# STM32F103c8t6.net
KiCad netlist of a schematic drawn in EasyEDA Pro
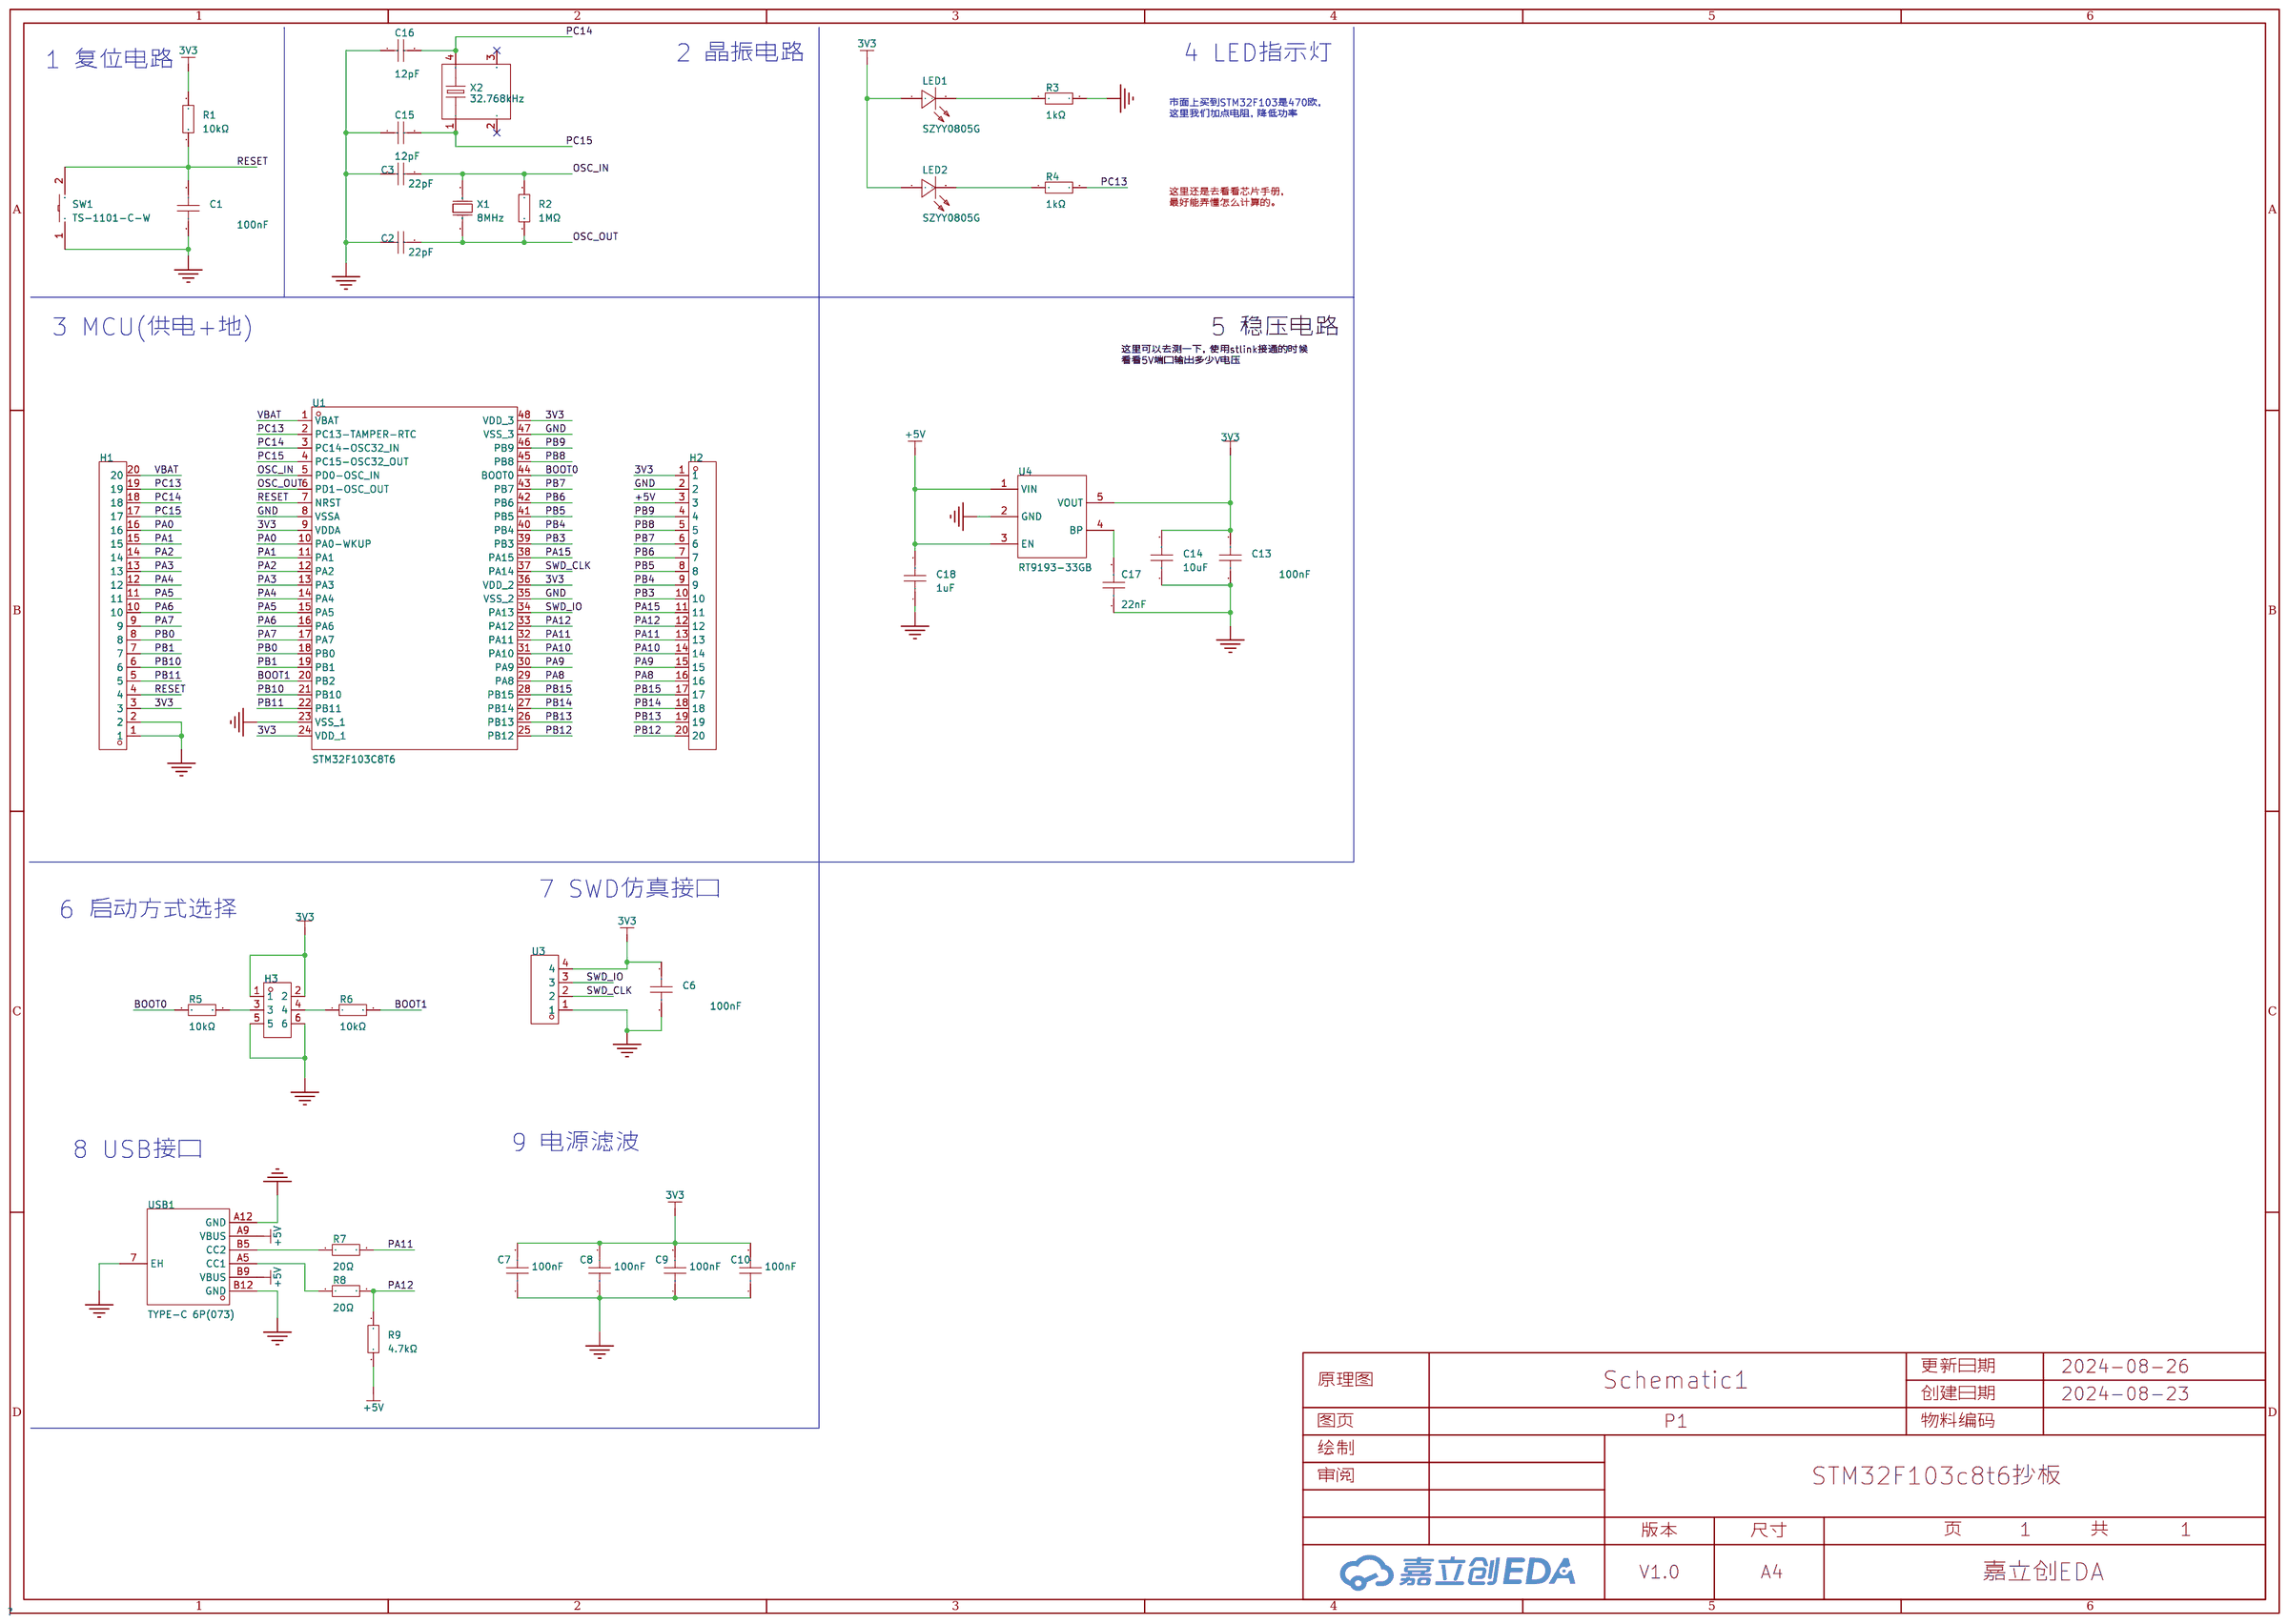
[diagram p0: schematic sheet]

(export (version "E")
  (design (tool "Eeschema 10.0.6"))
  (components
    (comp (ref "C1")
      (value "100nF")
      (footprint "easyedapro:C0603")
      (description "容值:100nF;精度:±10%;额定电压:50V;材质(温度系数):X7R;")
      (fields
        (field (name "Manufacturer Part") "CGA0603X7R104K500JT")
        (field (name "Manufacturer") "HRE(芯声)")
      )
      (libsource (lib "easyedapro") (part "CGA0603X7R104K500JT"))
    )
    (comp (ref "C2")
      (value "22pF")
      (footprint "easyedapro:C0603")
      (description "容值:22pF;精度:±5%;额定电压:50V;材质(温度系数):C0G;")
      (fields
        (field (name "Manufacturer Part") "CL10C220JB8NNNC")
        (field (name "Manufacturer") "SAMSUNG(三星)")
      )
      (libsource (lib "easyedapro") (part "CL10C220JB8NNNC"))
    )
    (comp (ref "C3")
      (value "22pF")
      (footprint "easyedapro:C0603")
      (description "容值:22pF;精度:±5%;额定电压:50V;材质(温度系数):C0G;")
      (fields
        (field (name "Manufacturer Part") "CL10C220JB8NNNC")
        (field (name "Manufacturer") "SAMSUNG(三星)")
      )
      (libsource (lib "easyedapro") (part "CL10C220JB8NNNC"))
    )
    (comp (ref "C6")
      (value "100nF")
      (footprint "easyedapro:C0603")
      (description "容值:100nF;精度:±10%;额定电压:50V;材质(温度系数):X7R;")
      (fields
        (field (name "Manufacturer Part") "CGA0603X7R104K500JT")
        (field (name "Manufacturer") "HRE(芯声)")
      )
      (libsource (lib "easyedapro") (part "CGA0603X7R104K500JT"))
    )
    (comp (ref "C7")
      (value "100nF")
      (footprint "easyedapro:C0603")
      (description "容值:100nF;精度:±10%;额定电压:50V;材质(温度系数):X7R;")
      (fields
        (field (name "Manufacturer Part") "CGA0603X7R104K500JT")
        (field (name "Manufacturer") "HRE(芯声)")
      )
      (libsource (lib "easyedapro") (part "CGA0603X7R104K500JT"))
    )
    (comp (ref "C8")
      (value "100nF")
      (footprint "easyedapro:C0603")
      (description "容值:100nF;精度:±10%;额定电压:50V;材质(温度系数):X7R;")
      (fields
        (field (name "Manufacturer Part") "CGA0603X7R104K500JT")
        (field (name "Manufacturer") "HRE(芯声)")
      )
      (libsource (lib "easyedapro") (part "CGA0603X7R104K500JT"))
    )
    (comp (ref "C9")
      (value "100nF")
      (footprint "easyedapro:C0603")
      (description "容值:100nF;精度:±10%;额定电压:50V;材质(温度系数):X7R;")
      (fields
        (field (name "Manufacturer Part") "CGA0603X7R104K500JT")
        (field (name "Manufacturer") "HRE(芯声)")
      )
      (libsource (lib "easyedapro") (part "CGA0603X7R104K500JT"))
    )
    (comp (ref "C10")
      (value "100nF")
      (footprint "easyedapro:C0603")
      (description "容值:100nF;精度:±10%;额定电压:50V;材质(温度系数):X7R;")
      (fields
        (field (name "Manufacturer Part") "CGA0603X7R104K500JT")
        (field (name "Manufacturer") "HRE(芯声)")
      )
      (libsource (lib "easyedapro") (part "CGA0603X7R104K500JT"))
    )
    (comp (ref "C13")
      (value "100nF")
      (footprint "easyedapro:C0603")
      (description "容值:100nF;精度:±10%;额定电压:50V;材质(温度系数):X7R;")
      (fields
        (field (name "Manufacturer Part") "CGA0603X7R104K500JT")
        (field (name "Manufacturer") "HRE(芯声)")
      )
      (libsource (lib "easyedapro") (part "CGA0603X7R104K500JT"))
    )
    (comp (ref "C14")
      (value "10uF")
      (footprint "easyedapro:C0603")
      (description "容值:10uF;精度:±20%;额定电压:35V;材质(温度系数):X5R;")
      (fields
        (field (name "Manufacturer Part") "GRM188R6YA106MA73D")
        (field (name "Manufacturer") "muRata(村田)")
      )
      (libsource (lib "easyedapro") (part "GRM188R6YA106MA73D"))
    )
    (comp (ref "C15")
      (value "12pF")
      (footprint "easyedapro:C0603")
      (description "容值:12pF;精度:±5%;额定电压:50V;材质(温度系数):C0G;")
      (fields
        (field (name "Manufacturer Part") "CL10C120JB8NNNC")
        (field (name "Manufacturer") "SAMSUNG(三星)")
      )
      (libsource (lib "easyedapro") (part "CL10C120JB8NNNC"))
    )
    (comp (ref "C16")
      (value "12pF")
      (footprint "easyedapro:C0603")
      (description "容值:12pF;精度:±5%;额定电压:50V;材质(温度系数):C0G;")
      (fields
        (field (name "Manufacturer Part") "CL10C120JB8NNNC")
        (field (name "Manufacturer") "SAMSUNG(三星)")
      )
      (libsource (lib "easyedapro") (part "CL10C120JB8NNNC"))
    )
    (comp (ref "C17")
      (value "22nF")
      (footprint "easyedapro:C0603")
      (description "容值:22nF;精度:±10%;额定电压:100V;材质(温度系数):X7R;")
      (fields
        (field (name "Manufacturer Part") "CC0603KRX7R0BB223")
        (field (name "Manufacturer") "YAGEO(国巨)")
      )
      (libsource (lib "easyedapro") (part "CC0603KRX7R0BB223"))
    )
    (comp (ref "C18")
      (value "1uF")
      (footprint "easyedapro:C0603")
      (description "容值:1uF;精度:±10%;额定电压:50V;材质(温度系数):X5R;")
      (fields
        (field (name "Manufacturer Part") "CL10A105KB8NNNC")
        (field (name "Manufacturer") "SAMSUNG(三星)")
      )
      (libsource (lib "easyedapro") (part "CL10A105KB8NNNC"))
    )
    (comp (ref "H1")
      (value "X6511WV-20H-C60D30")
      (footprint "easyedapro:HDR-TH_20P-P2.54-V-M")
      (fields (field (name "Manufacturer") "XKB Connection(中国星坤)"))
      (libsource (lib "easyedapro") (part "X6511WV-20H-C30D60"))
    )
    (comp (ref "H2")
      (value "X6511WV-20H-C60D30")
      (footprint "easyedapro:HDR-TH_20P-P2.54-V-M")
      (fields (field (name "Manufacturer") "XKB Connection(中国星坤)"))
      (libsource (lib "easyedapro") (part "X6511WV-20H-C30D60"))
    )
    (comp (ref "H3")
      (value "PZ254-2-03-Z-8.5")
      (footprint "easyedapro:HDR-TH_6P-P2.54-V-M-R2-C3-S2.54")
      (fields (field (name "Manufacturer") "HCTL(华灿天禄)"))
      (libsource (lib "easyedapro") (part "PZ254-2-03-Z-8.5"))
    )
    (comp (ref "LED1")
      (value "SZYY0805G")
      (footprint "easyedapro:LED0805-R-RD")
      (description "发光颜色:翠绿色;")
      (fields (field (name "Manufacturer") "yongyu(永裕光电)"))
      (libsource (lib "easyedapro") (part "SZYY0805G"))
    )
    (comp (ref "LED2")
      (value "SZYY0805G")
      (footprint "easyedapro:LED0805-R-RD")
      (description "发光颜色:翠绿色;")
      (fields (field (name "Manufacturer") "yongyu(永裕光电)"))
      (libsource (lib "easyedapro") (part "SZYY0805G"))
    )
    (comp (ref "R1")
      (value "10kΩ")
      (footprint "easyedapro:R0603")
      (description "电阻类型:厚膜电阻;阻值:10kΩ;精度:±1%;功率:100mW;最大工作电压:75V;温度系数:±100ppm/°C;")
      (fields
        (field (name "Manufacturer Part") "0603WAF1002T5E")
        (field (name "Manufacturer") "UNI-ROYAL(厚声)")
      )
      (libsource (lib "easyedapro") (part "0603WAF1002T5E"))
    )
    (comp (ref "R2")
      (value "1MΩ")
      (footprint "easyedapro:R0603")
      (description "电阻类型:厚膜电阻;阻值:1MΩ;精度:±1%;功率:100mW;最大工作电压:75V;温度系数:±100ppm/°C;")
      (fields
        (field (name "Manufacturer Part") "0603WAF1004T5E")
        (field (name "Manufacturer") "UNI-ROYAL(厚声)")
      )
      (libsource (lib "easyedapro") (part "0603WAF1004T5E"))
    )
    (comp (ref "R3")
      (value "1kΩ")
      (footprint "easyedapro:R0603")
      (description "电阻类型:厚膜电阻;阻值:1kΩ;精度:±1%;功率:100mW;最大工作电压:75V;温度系数:±100ppm/°C;")
      (fields
        (field (name "Manufacturer Part") "0603WAF1001T5E")
        (field (name "Manufacturer") "UNI-ROYAL(厚声)")
      )
      (libsource (lib "easyedapro") (part "0603WAF1001T5E"))
    )
    (comp (ref "R4")
      (value "1kΩ")
      (footprint "easyedapro:R0603")
      (description "电阻类型:厚膜电阻;阻值:1kΩ;精度:±1%;功率:100mW;最大工作电压:75V;温度系数:±100ppm/°C;")
      (fields
        (field (name "Manufacturer Part") "0603WAF1001T5E")
        (field (name "Manufacturer") "UNI-ROYAL(厚声)")
      )
      (libsource (lib "easyedapro") (part "0603WAF1001T5E"))
    )
    (comp (ref "R5")
      (value "10kΩ")
      (footprint "easyedapro:R0603")
      (description "电阻类型:厚膜电阻;阻值:10kΩ;精度:±1%;功率:100mW;最大工作电压:75V;温度系数:±100ppm/°C;")
      (fields
        (field (name "Manufacturer Part") "0603WAF1002T5E")
        (field (name "Manufacturer") "UNI-ROYAL(厚声)")
      )
      (libsource (lib "easyedapro") (part "0603WAF1002T5E"))
    )
    (comp (ref "R6")
      (value "10kΩ")
      (footprint "easyedapro:R0603")
      (description "电阻类型:厚膜电阻;阻值:10kΩ;精度:±1%;功率:100mW;最大工作电压:75V;温度系数:±100ppm/°C;")
      (fields
        (field (name "Manufacturer Part") "0603WAF1002T5E")
        (field (name "Manufacturer") "UNI-ROYAL(厚声)")
      )
      (libsource (lib "easyedapro") (part "0603WAF1002T5E"))
    )
    (comp (ref "R7")
      (value "20Ω")
      (footprint "easyedapro:R0603")
      (description "电阻类型:厚膜电阻;阻值:20Ω;精度:±1%;功率:100mW;最大工作电压:75V;温度系数:±100ppm/°C;")
      (fields
        (field (name "Manufacturer Part") "0603WAF200JT5E")
        (field (name "Manufacturer") "UNI-ROYAL(厚声)")
      )
      (libsource (lib "easyedapro") (part "0603WAF200JT5E"))
    )
    (comp (ref "R8")
      (value "20Ω")
      (footprint "easyedapro:R0603")
      (description "电阻类型:厚膜电阻;阻值:20Ω;精度:±1%;功率:100mW;最大工作电压:75V;温度系数:±100ppm/°C;")
      (fields
        (field (name "Manufacturer Part") "0603WAF200JT5E")
        (field (name "Manufacturer") "UNI-ROYAL(厚声)")
      )
      (libsource (lib "easyedapro") (part "0603WAF200JT5E"))
    )
    (comp (ref "R9")
      (value "4.7kΩ")
      (footprint "easyedapro:R0603")
      (description "电阻类型:厚膜电阻;阻值:4.7kΩ;精度:±1%;功率:100mW;最大工作电压:75V;温度系数:±100ppm/°C;")
      (fields
        (field (name "Manufacturer Part") "0603WAF4701T5E")
        (field (name "Manufacturer") "UNI-ROYAL(厚声)")
      )
      (libsource (lib "easyedapro") (part "0603WAF4701T5E"))
    )
    (comp (ref "SW1")
      (value "TS-1101-C-W")
      (footprint "easyedapro:SW-SMD_L6.0-W3.3-LS8.0")
      (fields (field (name "Manufacturer") "XKB Connectivity(中国星坤)"))
      (libsource (lib "easyedapro") (part "TS-1101-C-W"))
    )
    (comp (ref "U1")
      (value "STM32F103C8T6")
      (footprint "easyedapro:LQFP-48_L7.0-W7.0-P0.50-LS9.0-BL")
      (description "CPU内核:ARM-M3;程序存储容量:64KB;RAM总容量:20KB;GPIO端口数量:37;工作电压范围:2V~3.6V;CPU最大主频:72MHz;程序存储器类型:FLASH;")
      (fields (field (name "Manufacturer") "ST(意法半导体)"))
      (libsource (lib "easyedapro") (part "STM32F103C8T6"))
    )
    (comp (ref "U3")
      (value "HB-PH3-25414PB2GOP")
      (footprint "easyedapro:HDR-TH_4P-P2.54-V-M")
      (fields (field (name "Manufacturer") "HANBO(汉博)"))
      (libsource (lib "easyedapro") (part "HB-PH3-25414PB2GOP"))
    )
    (comp (ref "U4")
      (value "RT9193-33GB")
      (footprint "easyedapro:SOT-23-5_L3.0-W1.7-P0.95-LS2.8-BL")
      (description "输出类型:固定;最大输入电压:5.5V;输出电压:3.3V;最大输出电流:300mA;电源纹波抑制比(PSRR):70dB;输出极性:正极;")
      (fields (field (name "Manufacturer") "RICHTEK(立锜)"))
      (libsource (lib "easyedapro") (part "RT9193-33GB"))
    )
    (comp (ref "USB1")
      (value "TYPE-C 6P(073)")
      (footprint "easyedapro:TYPE-C-SMD_TYPE-C-6P_5")
      (description "连接器类型:Type-C;标准:-;公母:母;端口数量:1;触点数量:6P;安装方式:卧贴;额定电流 - 电源:5A;工作温度范围:-25°C~+85°C;")
      (fields (field (name "Manufacturer") "SHOU HAN(首韩)"))
      (libsource (lib "easyedapro") (part "TYPE-C 6P(073)"))
    )
    (comp (ref "X1")
      (value "8MHz")
      (footprint "easyedapro:OSC-TH_L10.0-W4.5-P5.00")
      (description "晶振类型:直插晶振;频率:8MHz;常温频差:±20ppm;外接负载电容:20pF;频率稳定度(全温):±30ppm;")
      (fields (field (name "Manufacturer Part") "X49SD8MSD2SC") (field (name "Manufacturer") "YXC(扬兴晶振)"))
      (libsource (lib "easyedapro") (part "X49SD8MSD2SC"))
    )
    (comp (ref "X2")
      (value "32.768kHz")
      (footprint "easyedapro:MC-306_4P-L8.0-W3.2-P5.5-BL")
      (description "晶振类型:贴片晶振;频率:32.768kHz;常温频差:±20ppm;外接负载电容:6pF;")
      (fields (field (name "Manufacturer Part") "Q13MC30620006") (field (name "Manufacturer") "EPSON(爱普生)"))
      (libsource (lib "easyedapro") (part "MC-306 32.768kHz 6.0pF 20ppm"))
    )
  )
  (nets
    (net (code "1") (name "+5V") (class "Default")
      (node (ref "C18") (pin "2") (pinfunction "2_2") (pintype "unspecified"))
      (node (ref "H2") (pin "3") (pinfunction "3_3") (pintype "unspecified"))
      (node (ref "R9") (pin "1") (pinfunction "1_1") (pintype "input"))
      (node (ref "U4") (pin "1") (pinfunction "VIN_1") (pintype "unspecified"))
      (node (ref "U4") (pin "3") (pinfunction "EN_3") (pintype "unspecified"))
      (node (ref "USB1") (pin "A9") (pinfunction "VBUS_A9") (pintype "unspecified"))
      (node (ref "USB1") (pin "B9") (pinfunction "VBUS_B9") (pintype "unspecified"))
    )
    (net (code "2") (name "/BOOT0") (class "Default")
      (node (ref "R5") (pin "1") (pinfunction "1_1") (pintype "input"))
      (node (ref "U1") (pin "44") (pinfunction "BOOT0_44") (pintype "unspecified"))
    )
    (net (code "3") (name "/BOOT1") (class "Default")
      (node (ref "R6") (pin "2") (pinfunction "2_2") (pintype "input"))
      (node (ref "U1") (pin "20") (pinfunction "PB2_20") (pintype "unspecified"))
    )
    (net (code "4") (name "/OSC_IN") (class "Default")
      (node (ref "C3") (pin "2") (pinfunction "2_2") (pintype "input"))
      (node (ref "R2") (pin "2") (pinfunction "2_2") (pintype "input"))
      (node (ref "U1") (pin "5") (pinfunction "PD0-OSC_IN_5") (pintype "unspecified"))
      (node (ref "X1") (pin "1") (pinfunction "OSC1_1") (pintype "input"))
    )
    (net (code "5") (name "/OSC_OUT") (class "Default")
      (node (ref "C2") (pin "2") (pinfunction "2_2") (pintype "input"))
      (node (ref "R2") (pin "1") (pinfunction "1_1") (pintype "input"))
      (node (ref "U1") (pin "6") (pinfunction "PD1-OSC_OUT_6") (pintype "unspecified"))
      (node (ref "X1") (pin "2") (pinfunction "OSC2_2") (pintype "input"))
    )
    (net (code "6") (name "/PA0") (class "Default")
      (node (ref "H1") (pin "16") (pinfunction "16_16") (pintype "unspecified"))
      (node (ref "U1") (pin "10") (pinfunction "PA0-WKUP_10") (pintype "unspecified"))
    )
    (net (code "7") (name "/PA1") (class "Default")
      (node (ref "H1") (pin "15") (pinfunction "15_15") (pintype "unspecified"))
      (node (ref "U1") (pin "11") (pinfunction "PA1_11") (pintype "unspecified"))
    )
    (net (code "8") (name "/PA2") (class "Default")
      (node (ref "H1") (pin "14") (pinfunction "14_14") (pintype "unspecified"))
      (node (ref "U1") (pin "12") (pinfunction "PA2_12") (pintype "unspecified"))
    )
    (net (code "9") (name "/PA3") (class "Default")
      (node (ref "H1") (pin "13") (pinfunction "13_13") (pintype "unspecified"))
      (node (ref "U1") (pin "13") (pinfunction "PA3_13") (pintype "unspecified"))
    )
    (net (code "10") (name "/PA4") (class "Default")
      (node (ref "H1") (pin "12") (pinfunction "12_12") (pintype "unspecified"))
      (node (ref "U1") (pin "14") (pinfunction "PA4_14") (pintype "unspecified"))
    )
    (net (code "11") (name "/PA5") (class "Default")
      (node (ref "H1") (pin "11") (pinfunction "11_11") (pintype "unspecified"))
      (node (ref "U1") (pin "15") (pinfunction "PA5_15") (pintype "unspecified"))
    )
    (net (code "12") (name "/PA6") (class "Default")
      (node (ref "H1") (pin "10") (pinfunction "10_10") (pintype "unspecified"))
      (node (ref "U1") (pin "16") (pinfunction "PA6_16") (pintype "unspecified"))
    )
    (net (code "13") (name "/PA7") (class "Default")
      (node (ref "H1") (pin "9") (pinfunction "9_9") (pintype "unspecified"))
      (node (ref "U1") (pin "17") (pinfunction "PA7_17") (pintype "unspecified"))
    )
    (net (code "14") (name "/PA8") (class "Default")
      (node (ref "H2") (pin "16") (pinfunction "16_16") (pintype "unspecified"))
      (node (ref "U1") (pin "29") (pinfunction "PA8_29") (pintype "unspecified"))
    )
    (net (code "15") (name "/PA9") (class "Default")
      (node (ref "H2") (pin "15") (pinfunction "15_15") (pintype "unspecified"))
      (node (ref "U1") (pin "30") (pinfunction "PA9_30") (pintype "unspecified"))
    )
    (net (code "16") (name "/PA10") (class "Default")
      (node (ref "H2") (pin "14") (pinfunction "14_14") (pintype "unspecified"))
      (node (ref "U1") (pin "31") (pinfunction "PA10_31") (pintype "unspecified"))
    )
    (net (code "17") (name "/PA11") (class "Default")
      (node (ref "H2") (pin "13") (pinfunction "13_13") (pintype "unspecified"))
      (node (ref "R7") (pin "2") (pinfunction "2_2") (pintype "input"))
      (node (ref "U1") (pin "32") (pinfunction "PA11_32") (pintype "unspecified"))
    )
    (net (code "18") (name "/PA12") (class "Default")
      (node (ref "H2") (pin "12") (pinfunction "12_12") (pintype "unspecified"))
      (node (ref "R8") (pin "2") (pinfunction "2_2") (pintype "input"))
      (node (ref "R9") (pin "2") (pinfunction "2_2") (pintype "input"))
      (node (ref "U1") (pin "33") (pinfunction "PA12_33") (pintype "unspecified"))
    )
    (net (code "19") (name "/PA15") (class "Default")
      (node (ref "H2") (pin "11") (pinfunction "11_11") (pintype "unspecified"))
      (node (ref "U1") (pin "38") (pinfunction "PA15_38") (pintype "unspecified"))
    )
    (net (code "20") (name "/PB0") (class "Default")
      (node (ref "H1") (pin "8") (pinfunction "8_8") (pintype "unspecified"))
      (node (ref "U1") (pin "18") (pinfunction "PB0_18") (pintype "unspecified"))
    )
    (net (code "21") (name "/PB1") (class "Default")
      (node (ref "H1") (pin "7") (pinfunction "7_7") (pintype "unspecified"))
      (node (ref "U1") (pin "19") (pinfunction "PB1_19") (pintype "unspecified"))
    )
    (net (code "22") (name "/PB3") (class "Default")
      (node (ref "H2") (pin "10") (pinfunction "10_10") (pintype "unspecified"))
      (node (ref "U1") (pin "39") (pinfunction "PB3_39") (pintype "unspecified"))
    )
    (net (code "23") (name "/PB4") (class "Default")
      (node (ref "H2") (pin "9") (pinfunction "9_9") (pintype "unspecified"))
      (node (ref "U1") (pin "40") (pinfunction "PB4_40") (pintype "unspecified"))
    )
    (net (code "24") (name "/PB5") (class "Default")
      (node (ref "H2") (pin "8") (pinfunction "8_8") (pintype "unspecified"))
      (node (ref "U1") (pin "41") (pinfunction "PB5_41") (pintype "unspecified"))
    )
    (net (code "25") (name "/PB6") (class "Default")
      (node (ref "H2") (pin "7") (pinfunction "7_7") (pintype "unspecified"))
      (node (ref "U1") (pin "42") (pinfunction "PB6_42") (pintype "unspecified"))
    )
    (net (code "26") (name "/PB7") (class "Default")
      (node (ref "H2") (pin "6") (pinfunction "6_6") (pintype "unspecified"))
      (node (ref "U1") (pin "43") (pinfunction "PB7_43") (pintype "unspecified"))
    )
    (net (code "27") (name "/PB8") (class "Default")
      (node (ref "H2") (pin "5") (pinfunction "5_5") (pintype "unspecified"))
      (node (ref "U1") (pin "45") (pinfunction "PB8_45") (pintype "unspecified"))
    )
    (net (code "28") (name "/PB9") (class "Default")
      (node (ref "H2") (pin "4") (pinfunction "4_4") (pintype "unspecified"))
      (node (ref "U1") (pin "46") (pinfunction "PB9_46") (pintype "unspecified"))
    )
    (net (code "29") (name "/PB10") (class "Default")
      (node (ref "H1") (pin "6") (pinfunction "6_6") (pintype "unspecified"))
      (node (ref "U1") (pin "21") (pinfunction "PB10_21") (pintype "unspecified"))
    )
    (net (code "30") (name "/PB11") (class "Default")
      (node (ref "H1") (pin "5") (pinfunction "5_5") (pintype "unspecified"))
      (node (ref "U1") (pin "22") (pinfunction "PB11_22") (pintype "unspecified"))
    )
    (net (code "31") (name "/PB12") (class "Default")
      (node (ref "H2") (pin "20") (pinfunction "20_20") (pintype "unspecified"))
      (node (ref "U1") (pin "25") (pinfunction "PB12_25") (pintype "unspecified"))
    )
    (net (code "32") (name "/PB13") (class "Default")
      (node (ref "H2") (pin "19") (pinfunction "19_19") (pintype "unspecified"))
      (node (ref "U1") (pin "26") (pinfunction "PB13_26") (pintype "unspecified"))
    )
    (net (code "33") (name "/PB14") (class "Default")
      (node (ref "H2") (pin "18") (pinfunction "18_18") (pintype "unspecified"))
      (node (ref "U1") (pin "27") (pinfunction "PB14_27") (pintype "unspecified"))
    )
    (net (code "34") (name "/PB15") (class "Default")
      (node (ref "H2") (pin "17") (pinfunction "17_17") (pintype "unspecified"))
      (node (ref "U1") (pin "28") (pinfunction "PB15_28") (pintype "unspecified"))
    )
    (net (code "35") (name "/PC13") (class "Default")
      (node (ref "H1") (pin "19") (pinfunction "19_19") (pintype "unspecified"))
      (node (ref "R4") (pin "2") (pinfunction "2_2") (pintype "input"))
      (node (ref "U1") (pin "2") (pinfunction "PC13-TAMPER-RTC_2") (pintype "unspecified"))
    )
    (net (code "36") (name "/PC14") (class "Default")
      (node (ref "C16") (pin "2") (pinfunction "2_2") (pintype "input"))
      (node (ref "H1") (pin "18") (pinfunction "18_18") (pintype "unspecified"))
      (node (ref "U1") (pin "3") (pinfunction "PC14-OSC32_IN_3") (pintype "unspecified"))
      (node (ref "X2") (pin "4") (pinfunction "4_4") (pintype "unspecified"))
    )
    (net (code "37") (name "/PC15") (class "Default")
      (node (ref "C15") (pin "2") (pinfunction "2_2") (pintype "input"))
      (node (ref "H1") (pin "17") (pinfunction "17_17") (pintype "unspecified"))
      (node (ref "U1") (pin "4") (pinfunction "PC15-OSC32_OUT_4") (pintype "unspecified"))
      (node (ref "X2") (pin "1") (pinfunction "1_1") (pintype "unspecified"))
    )
    (net (code "38") (name "/RESET") (class "Default")
      (node (ref "C1") (pin "2") (pinfunction "2_2") (pintype "unspecified"))
      (node (ref "H1") (pin "4") (pinfunction "4_4") (pintype "unspecified"))
      (node (ref "R1") (pin "1") (pinfunction "1_1") (pintype "input"))
      (node (ref "SW1") (pin "2") (pinfunction "2_2") (pintype "unspecified"))
      (node (ref "U1") (pin "7") (pinfunction "NRST_7") (pintype "unspecified"))
    )
    (net (code "39") (name "/SWD_CLK") (class "Default")
      (node (ref "U1") (pin "37") (pinfunction "PA14_37") (pintype "unspecified"))
      (node (ref "U3") (pin "2") (pinfunction "2_2") (pintype "unspecified"))
    )
    (net (code "40") (name "/SWD_IO") (class "Default")
      (node (ref "U1") (pin "34") (pinfunction "PA13_34") (pintype "unspecified"))
      (node (ref "U3") (pin "3") (pinfunction "3_3") (pintype "unspecified"))
    )
    (net (code "41") (name "/VBAT") (class "Default")
      (node (ref "H1") (pin "20") (pinfunction "20_20") (pintype "unspecified"))
      (node (ref "U1") (pin "1") (pinfunction "VBAT_1") (pintype "unspecified"))
    )
    (net (code "42") (name "3V3") (class "Default")
      (node (ref "C10") (pin "2") (pinfunction "2_2") (pintype "unspecified"))
      (node (ref "C13") (pin "2") (pinfunction "2_2") (pintype "unspecified"))
      (node (ref "C14") (pin "2") (pinfunction "2_2") (pintype "input"))
      (node (ref "C6") (pin "2") (pinfunction "2_2") (pintype "unspecified"))
      (node (ref "C7") (pin "2") (pinfunction "2_2") (pintype "unspecified"))
      (node (ref "C8") (pin "2") (pinfunction "2_2") (pintype "unspecified"))
      (node (ref "C9") (pin "2") (pinfunction "2_2") (pintype "unspecified"))
      (node (ref "H1") (pin "3") (pinfunction "3_3") (pintype "unspecified"))
      (node (ref "H2") (pin "1") (pinfunction "1_1") (pintype "unspecified"))
      (node (ref "H3") (pin "1") (pinfunction "1_1") (pintype "unspecified"))
      (node (ref "H3") (pin "2") (pinfunction "2_2") (pintype "unspecified"))
      (node (ref "LED1") (pin "1") (pinfunction "+_1") (pintype "unspecified"))
      (node (ref "LED2") (pin "1") (pinfunction "+_1") (pintype "unspecified"))
      (node (ref "R1") (pin "2") (pinfunction "2_2") (pintype "input"))
      (node (ref "U1") (pin "24") (pinfunction "VDD_1_24") (pintype "unspecified"))
      (node (ref "U1") (pin "36") (pinfunction "VDD_2_36") (pintype "unspecified"))
      (node (ref "U1") (pin "48") (pinfunction "VDD_3_48") (pintype "unspecified"))
      (node (ref "U1") (pin "9") (pinfunction "VDDA_9") (pintype "unspecified"))
      (node (ref "U3") (pin "4") (pinfunction "4_4") (pintype "unspecified"))
      (node (ref "U4") (pin "5") (pinfunction "VOUT_5") (pintype "unspecified"))
    )
    (net (code "43") (name "GND") (class "Default")
      (node (ref "C1") (pin "1") (pinfunction "1_1") (pintype "unspecified"))
      (node (ref "C10") (pin "1") (pinfunction "1_1") (pintype "unspecified"))
      (node (ref "C13") (pin "1") (pinfunction "1_1") (pintype "unspecified"))
      (node (ref "C14") (pin "1") (pinfunction "1_1") (pintype "input"))
      (node (ref "C15") (pin "1") (pinfunction "1_1") (pintype "input"))
      (node (ref "C16") (pin "1") (pinfunction "1_1") (pintype "input"))
      (node (ref "C17") (pin "1") (pinfunction "1_1") (pintype "input"))
      (node (ref "C18") (pin "1") (pinfunction "1_1") (pintype "unspecified"))
      (node (ref "C2") (pin "1") (pinfunction "1_1") (pintype "input"))
      (node (ref "C3") (pin "1") (pinfunction "1_1") (pintype "input"))
      (node (ref "C6") (pin "1") (pinfunction "1_1") (pintype "unspecified"))
      (node (ref "C7") (pin "1") (pinfunction "1_1") (pintype "unspecified"))
      (node (ref "C8") (pin "1") (pinfunction "1_1") (pintype "unspecified"))
      (node (ref "C9") (pin "1") (pinfunction "1_1") (pintype "unspecified"))
      (node (ref "H1") (pin "1") (pinfunction "1_1") (pintype "unspecified"))
      (node (ref "H1") (pin "2") (pinfunction "2_2") (pintype "unspecified"))
      (node (ref "H2") (pin "2") (pinfunction "2_2") (pintype "unspecified"))
      (node (ref "H3") (pin "5") (pinfunction "5_5") (pintype "unspecified"))
      (node (ref "H3") (pin "6") (pinfunction "6_6") (pintype "unspecified"))
      (node (ref "R3") (pin "2") (pinfunction "2_2") (pintype "input"))
      (node (ref "SW1") (pin "1") (pinfunction "1_1") (pintype "unspecified"))
      (node (ref "U1") (pin "23") (pinfunction "VSS_1_23") (pintype "unspecified"))
      (node (ref "U1") (pin "35") (pinfunction "VSS_2_35") (pintype "unspecified"))
      (node (ref "U1") (pin "47") (pinfunction "VSS_3_47") (pintype "unspecified"))
      (node (ref "U1") (pin "8") (pinfunction "VSSA_8") (pintype "unspecified"))
      (node (ref "U3") (pin "1") (pinfunction "1_1") (pintype "unspecified"))
      (node (ref "U4") (pin "2") (pinfunction "GND_2") (pintype "unspecified"))
      (node (ref "USB1") (pin "7") (pinfunction "EH_7") (pintype "unspecified"))
      (node (ref "USB1") (pin "A12") (pinfunction "GND_A12") (pintype "unspecified"))
      (node (ref "USB1") (pin "B12") (pinfunction "GND_B12") (pintype "unspecified"))
    )
    (net (code "44") (name "Net-(H3-Pad3)") (class "Default")
      (node (ref "H3") (pin "3") (pinfunction "3_3") (pintype "unspecified"))
      (node (ref "R5") (pin "2") (pinfunction "2_2") (pintype "input"))
    )
    (net (code "45") (name "Net-(H3-Pad4)") (class "Default")
      (node (ref "H3") (pin "4") (pinfunction "4_4") (pintype "unspecified"))
      (node (ref "R6") (pin "1") (pinfunction "1_1") (pintype "input"))
    )
    (net (code "46") (name "Net-(LED1--)") (class "Default")
      (node (ref "LED1") (pin "2") (pinfunction "-_2") (pintype "unspecified"))
      (node (ref "R3") (pin "1") (pinfunction "1_1") (pintype "input"))
    )
    (net (code "47") (name "Net-(LED2--)") (class "Default")
      (node (ref "LED2") (pin "2") (pinfunction "-_2") (pintype "unspecified"))
      (node (ref "R4") (pin "1") (pinfunction "1_1") (pintype "input"))
    )
    (net (code "48") (name "Net-(U4-BP)") (class "Default")
      (node (ref "C17") (pin "2") (pinfunction "2_2") (pintype "input"))
      (node (ref "U4") (pin "4") (pinfunction "BP_4") (pintype "unspecified"))
    )
    (net (code "49") (name "Net-(USB1-CC1)") (class "Default")
      (node (ref "R8") (pin "1") (pinfunction "1_1") (pintype "input"))
      (node (ref "USB1") (pin "A5") (pinfunction "CC1_A5") (pintype "unspecified"))
    )
    (net (code "50") (name "Net-(USB1-CC2)") (class "Default")
      (node (ref "R7") (pin "1") (pinfunction "1_1") (pintype "input"))
      (node (ref "USB1") (pin "B5") (pinfunction "CC2_B5") (pintype "unspecified"))
    )
    (net (code "51") (name "unconnected-(X2-Pad2)") (class "Default")
      (node (ref "X2") (pin "2") (pinfunction "2_2") (pintype "unspecified+no_connect"))
    )
    (net (code "52") (name "unconnected-(X2-Pad3)") (class "Default")
      (node (ref "X2") (pin "3") (pinfunction "3_3") (pintype "unspecified+no_connect"))
    )
  )
)
